# tdt_ysplitter.net
KiCad netlist of a schematic drawn in EAGLE
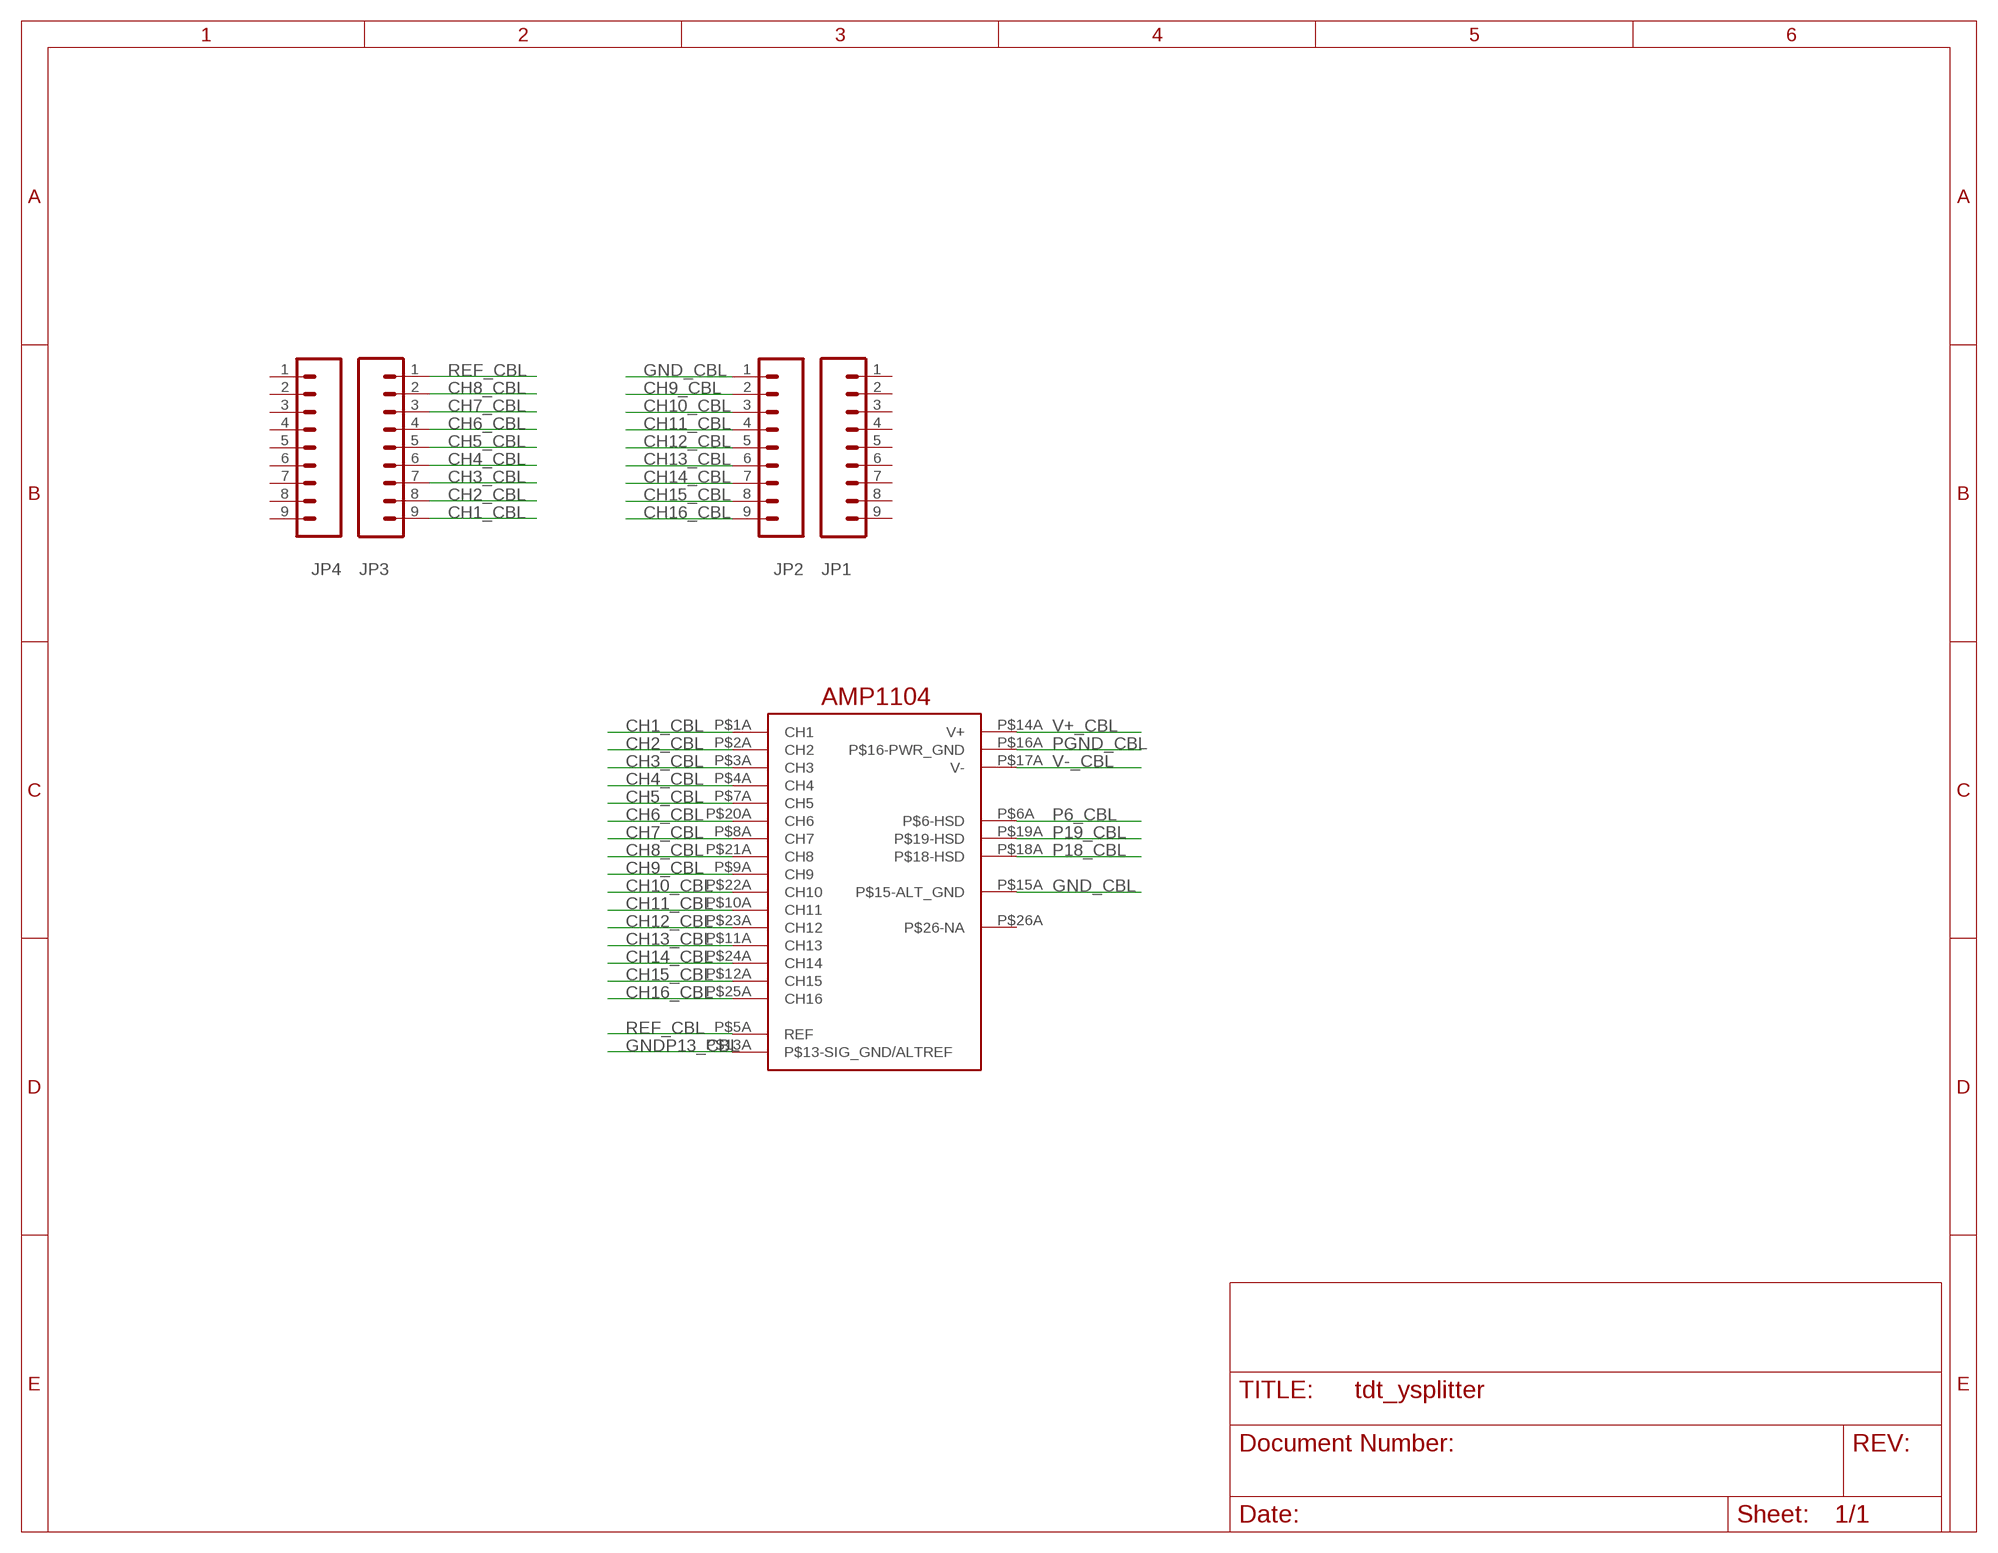
[diagram p0: schematic, sheet 1]

(export (version "E")
  (design (tool "Eeschema 10.0.6"))
  (components
    (comp (ref "JP1")
      (value "M09")
      (footprint "eagle-import:1X09")
      (libsource (lib "eagle-import") (part "M09"))
    )
    (comp (ref "JP2")
      (value "M09")
      (footprint "eagle-import:1X09")
      (libsource (lib "eagle-import") (part "M09"))
    )
    (comp (ref "JP3")
      (value "M09")
      (footprint "eagle-import:1X09")
      (libsource (lib "eagle-import") (part "M09"))
    )
    (comp (ref "JP4")
      (value "M09")
      (footprint "eagle-import:1X09")
      (libsource (lib "eagle-import") (part "M09"))
    )
    (comp (ref "U$3")
      (value "AMP1104")
      (footprint "eagle-import:AMP1104")
      (libsource (lib "eagle-import") (part "AMP1104"))
    )
  )
  (nets
    (net (code "1") (name "/CH1_CBL") (class "Default")
      (node (ref "JP3") (pin "9") (pinfunction "9_9") (pintype "passive"))
      (node (ref "U$3") (pin "P$1A") (pinfunction "CH1_P$1A") (pintype "bidirectional"))
    )
    (net (code "2") (name "/CH2_CBL") (class "Default")
      (node (ref "JP3") (pin "8") (pinfunction "8_8") (pintype "passive"))
      (node (ref "U$3") (pin "P$2A") (pinfunction "CH2_P$2A") (pintype "bidirectional"))
    )
    (net (code "3") (name "/CH3_CBL") (class "Default")
      (node (ref "JP3") (pin "7") (pinfunction "7_7") (pintype "passive"))
      (node (ref "U$3") (pin "P$3A") (pinfunction "CH3_P$3A") (pintype "bidirectional"))
    )
    (net (code "4") (name "/CH4_CBL") (class "Default")
      (node (ref "JP3") (pin "6") (pinfunction "6_6") (pintype "passive"))
      (node (ref "U$3") (pin "P$4A") (pinfunction "CH4_P$4A") (pintype "bidirectional"))
    )
    (net (code "5") (name "/CH5_CBL") (class "Default")
      (node (ref "JP3") (pin "5") (pinfunction "5_5") (pintype "passive"))
      (node (ref "U$3") (pin "P$7A") (pinfunction "CH5_P$7A") (pintype "bidirectional"))
    )
    (net (code "6") (name "/CH6_CBL") (class "Default")
      (node (ref "JP3") (pin "4") (pinfunction "4_4") (pintype "passive"))
      (node (ref "U$3") (pin "P$20A") (pinfunction "CH6_P$20A") (pintype "bidirectional"))
    )
    (net (code "7") (name "/CH7_CBL") (class "Default")
      (node (ref "JP3") (pin "3") (pinfunction "3_3") (pintype "passive"))
      (node (ref "U$3") (pin "P$8A") (pinfunction "CH7_P$8A") (pintype "bidirectional"))
    )
    (net (code "8") (name "/CH8_CBL") (class "Default")
      (node (ref "JP3") (pin "2") (pinfunction "2_2") (pintype "passive"))
      (node (ref "U$3") (pin "P$21A") (pinfunction "CH8_P$21A") (pintype "bidirectional"))
    )
    (net (code "9") (name "/CH9_CBL") (class "Default")
      (node (ref "JP2") (pin "2") (pinfunction "2_2") (pintype "passive"))
      (node (ref "U$3") (pin "P$9A") (pinfunction "CH9_P$9A") (pintype "bidirectional"))
    )
    (net (code "10") (name "/CH10_CBL") (class "Default")
      (node (ref "JP2") (pin "3") (pinfunction "3_3") (pintype "passive"))
      (node (ref "U$3") (pin "P$22A") (pinfunction "CH10_P$22A") (pintype "bidirectional"))
    )
    (net (code "11") (name "/CH11_CBL") (class "Default")
      (node (ref "JP2") (pin "4") (pinfunction "4_4") (pintype "passive"))
      (node (ref "U$3") (pin "P$10A") (pinfunction "CH11_P$10A") (pintype "bidirectional"))
    )
    (net (code "12") (name "/CH12_CBL") (class "Default")
      (node (ref "JP2") (pin "5") (pinfunction "5_5") (pintype "passive"))
      (node (ref "U$3") (pin "P$23A") (pinfunction "CH12_P$23A") (pintype "bidirectional"))
    )
    (net (code "13") (name "/CH13_CBL") (class "Default")
      (node (ref "JP2") (pin "6") (pinfunction "6_6") (pintype "passive"))
      (node (ref "U$3") (pin "P$11A") (pinfunction "CH13_P$11A") (pintype "bidirectional"))
    )
    (net (code "14") (name "/CH14_CBL") (class "Default")
      (node (ref "JP2") (pin "7") (pinfunction "7_7") (pintype "passive"))
      (node (ref "U$3") (pin "P$24A") (pinfunction "CH14_P$24A") (pintype "bidirectional"))
    )
    (net (code "15") (name "/CH15_CBL") (class "Default")
      (node (ref "JP2") (pin "8") (pinfunction "8_8") (pintype "passive"))
      (node (ref "U$3") (pin "P$12A") (pinfunction "CH15_P$12A") (pintype "bidirectional"))
    )
    (net (code "16") (name "/CH16_CBL") (class "Default")
      (node (ref "JP2") (pin "9") (pinfunction "9_9") (pintype "passive"))
      (node (ref "U$3") (pin "P$25A") (pinfunction "CH16_P$25A") (pintype "bidirectional"))
    )
    (net (code "17") (name "/GNDP13_CBL") (class "Default")
      (node (ref "U$3") (pin "P$13A") (pinfunction "P$13-SIG_GND/ALTREF_P$13A") (pintype "bidirectional"))
    )
    (net (code "18") (name "/GND_CBL") (class "Default")
      (node (ref "JP2") (pin "1") (pinfunction "1_1") (pintype "passive"))
      (node (ref "U$3") (pin "P$15A") (pinfunction "P$15-ALT_GND_P$15A") (pintype "bidirectional"))
    )
    (net (code "19") (name "/P6_CBL") (class "Default")
      (node (ref "U$3") (pin "P$6A") (pinfunction "P$6-HSD_P$6A") (pintype "bidirectional"))
    )
    (net (code "20") (name "/P18_CBL") (class "Default")
      (node (ref "U$3") (pin "P$18A") (pinfunction "P$18-HSD_P$18A") (pintype "bidirectional"))
    )
    (net (code "21") (name "/P19_CBL") (class "Default")
      (node (ref "U$3") (pin "P$19A") (pinfunction "P$19-HSD_P$19A") (pintype "bidirectional"))
    )
    (net (code "22") (name "/PGND_CBL") (class "Default")
      (node (ref "U$3") (pin "P$16A") (pinfunction "P$16-PWR_GND_P$16A") (pintype "bidirectional"))
    )
    (net (code "23") (name "/REF_CBL") (class "Default")
      (node (ref "JP3") (pin "1") (pinfunction "1_1") (pintype "passive"))
      (node (ref "U$3") (pin "P$5A") (pinfunction "REF_P$5A") (pintype "bidirectional"))
    )
    (net (code "24") (name "/V+_CBL") (class "Default")
      (node (ref "U$3") (pin "P$14A") (pinfunction "V+_P$14A") (pintype "bidirectional"))
    )
    (net (code "25") (name "/V-_CBL") (class "Default")
      (node (ref "U$3") (pin "P$17A") (pinfunction "V-_P$17A") (pintype "bidirectional"))
    )
    (net (code "26") (name "unconnected-(JP1-Pad1)") (class "Default")
      (node (ref "JP1") (pin "1") (pinfunction "1_1") (pintype "passive"))
    )
    (net (code "27") (name "unconnected-(JP1-Pad2)") (class "Default")
      (node (ref "JP1") (pin "2") (pinfunction "2_2") (pintype "passive"))
    )
    (net (code "28") (name "unconnected-(JP1-Pad3)") (class "Default")
      (node (ref "JP1") (pin "3") (pinfunction "3_3") (pintype "passive"))
    )
    (net (code "29") (name "unconnected-(JP1-Pad4)") (class "Default")
      (node (ref "JP1") (pin "4") (pinfunction "4_4") (pintype "passive"))
    )
    (net (code "30") (name "unconnected-(JP1-Pad5)") (class "Default")
      (node (ref "JP1") (pin "5") (pinfunction "5_5") (pintype "passive"))
    )
    (net (code "31") (name "unconnected-(JP1-Pad6)") (class "Default")
      (node (ref "JP1") (pin "6") (pinfunction "6_6") (pintype "passive"))
    )
    (net (code "32") (name "unconnected-(JP1-Pad7)") (class "Default")
      (node (ref "JP1") (pin "7") (pinfunction "7_7") (pintype "passive"))
    )
    (net (code "33") (name "unconnected-(JP1-Pad8)") (class "Default")
      (node (ref "JP1") (pin "8") (pinfunction "8_8") (pintype "passive"))
    )
    (net (code "34") (name "unconnected-(JP1-Pad9)") (class "Default")
      (node (ref "JP1") (pin "9") (pinfunction "9_9") (pintype "passive"))
    )
    (net (code "35") (name "unconnected-(JP4-Pad1)") (class "Default")
      (node (ref "JP4") (pin "1") (pinfunction "1_1") (pintype "passive"))
    )
    (net (code "36") (name "unconnected-(JP4-Pad2)") (class "Default")
      (node (ref "JP4") (pin "2") (pinfunction "2_2") (pintype "passive"))
    )
    (net (code "37") (name "unconnected-(JP4-Pad3)") (class "Default")
      (node (ref "JP4") (pin "3") (pinfunction "3_3") (pintype "passive"))
    )
    (net (code "38") (name "unconnected-(JP4-Pad4)") (class "Default")
      (node (ref "JP4") (pin "4") (pinfunction "4_4") (pintype "passive"))
    )
    (net (code "39") (name "unconnected-(JP4-Pad5)") (class "Default")
      (node (ref "JP4") (pin "5") (pinfunction "5_5") (pintype "passive"))
    )
    (net (code "40") (name "unconnected-(JP4-Pad6)") (class "Default")
      (node (ref "JP4") (pin "6") (pinfunction "6_6") (pintype "passive"))
    )
    (net (code "41") (name "unconnected-(JP4-Pad7)") (class "Default")
      (node (ref "JP4") (pin "7") (pinfunction "7_7") (pintype "passive"))
    )
    (net (code "42") (name "unconnected-(JP4-Pad8)") (class "Default")
      (node (ref "JP4") (pin "8") (pinfunction "8_8") (pintype "passive"))
    )
    (net (code "43") (name "unconnected-(JP4-Pad9)") (class "Default")
      (node (ref "JP4") (pin "9") (pinfunction "9_9") (pintype "passive"))
    )
    (net (code "44") (name "unconnected-(U$3-P$26-NA-PadP$26A)") (class "Default")
      (node (ref "U$3") (pin "P$26A") (pinfunction "P$26-NA_P$26A") (pintype "bidirectional"))
    )
  )
)
